# DSP_Power.net
KiCad netlist of a schematic drawn in Altium Designer
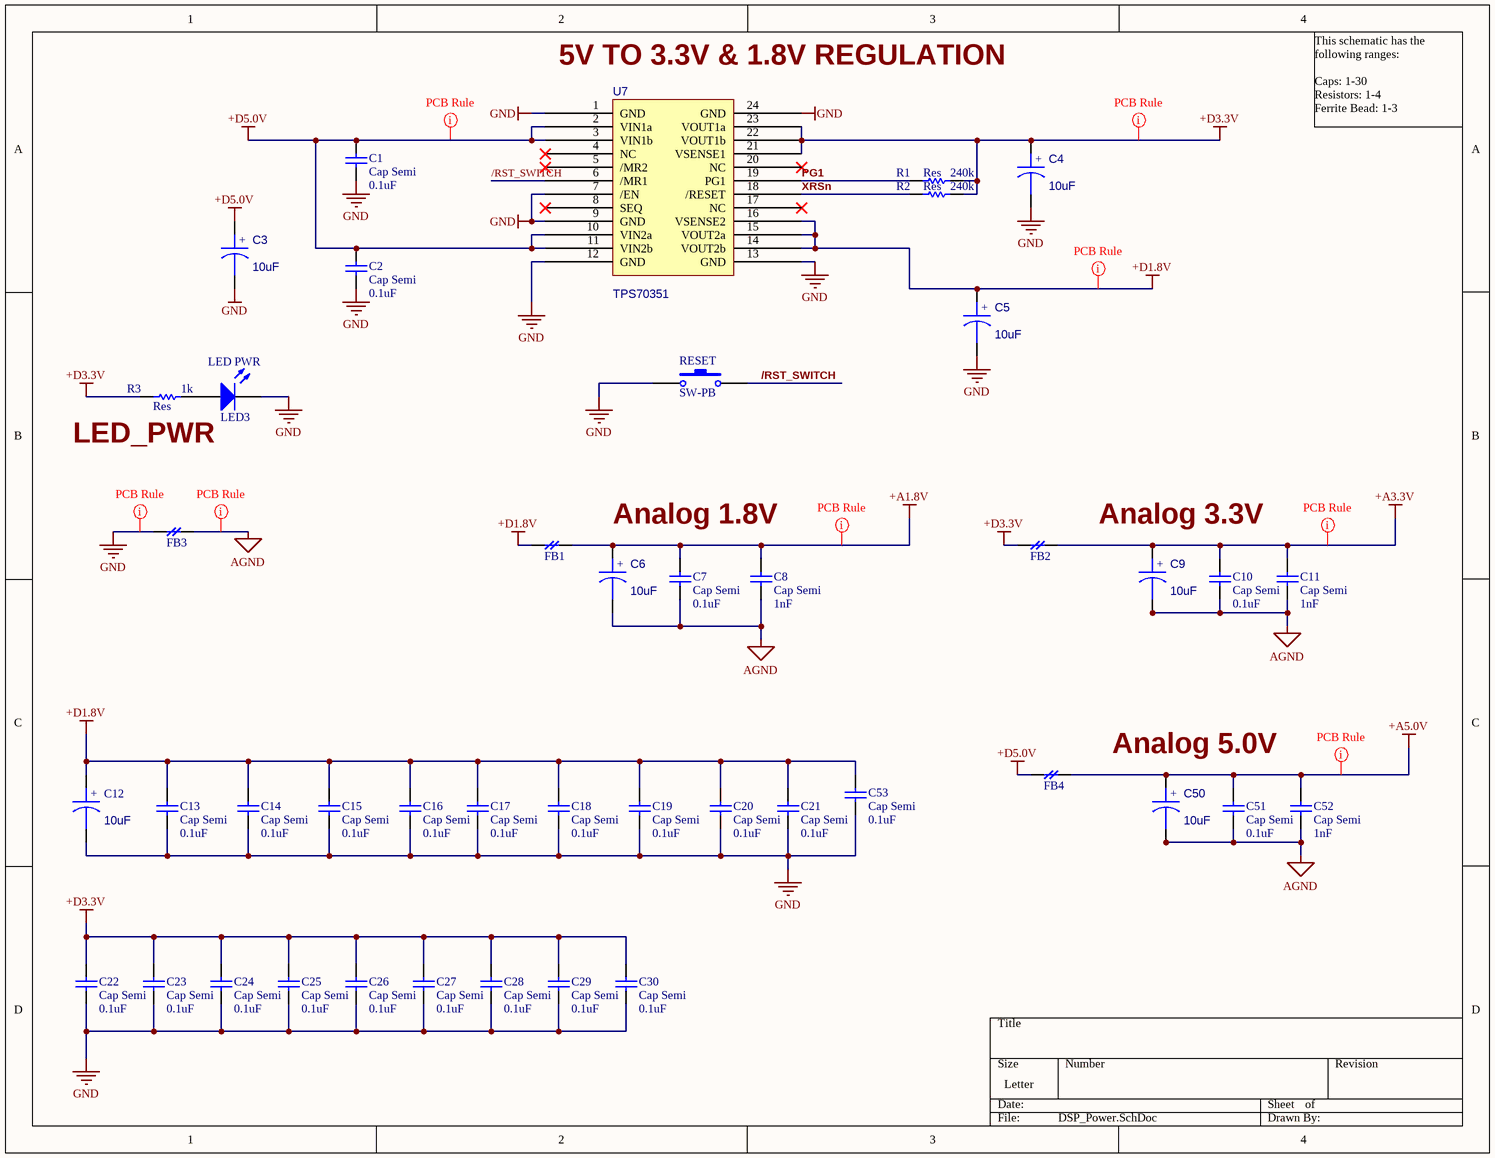
[diagram p0: DSP_Power.SchDoc]

(export (version "E")
  (design (tool "Eeschema 10.0.6"))
  (components
    (comp (ref "C1")
      (value "Cap Semi")
      (footprint "0805")
      (description "Capacitor (Semiconductor SIM Model)")
      (fields (field (name "ALTIUM_VALUE") "0.1uF") (field (name "PUBLISHER") "Altium Limited"))
      (libsource (lib "Miscellaneous Devices") (part "Cap Semi"))
    )
    (comp (ref "C2")
      (value "Cap Semi")
      (footprint "0805")
      (description "Capacitor (Semiconductor SIM Model)")
      (fields (field (name "ALTIUM_VALUE") "0.1uF") (field (name "PUBLISHER") "Altium Limited"))
      (libsource (lib "Miscellaneous Devices") (part "Cap Semi"))
    )
    (comp (ref "C3")
      (value "10uF")
      (footprint "3528")
      (description "digi-399-1563-1-ND")
      (libsource (lib "*") (part "CAPACITOR POL"))
    )
    (comp (ref "C4")
      (value "10uF")
      (footprint "3528")
      (description "digi-399-3096-1-ND")
      (libsource (lib "*") (part "CAPACITOR POL"))
    )
    (comp (ref "C5")
      (value "10uF")
      (footprint "3528")
      (description "digi-399-1576-1-ND")
      (libsource (lib "*") (part "CAPACITOR POL"))
    )
    (comp (ref "C6")
      (value "10uF")
      (footprint "3528")
      (description "digi-399-3096-1-ND")
      (libsource (lib "*") (part "CAPACITOR POL"))
    )
    (comp (ref "C7")
      (value "Cap Semi")
      (footprint "0805")
      (description "Capacitor (Semiconductor SIM Model)")
      (fields (field (name "ALTIUM_VALUE") "0.1uF") (field (name "PUBLISHER") "Altium Limited"))
      (libsource (lib "Miscellaneous Devices") (part "Cap Semi"))
    )
    (comp (ref "C8")
      (value "Cap Semi")
      (footprint "0805")
      (description "Capacitor (Semiconductor SIM Model)")
      (fields (field (name "ALTIUM_VALUE") "1nF") (field (name "PUBLISHER") "Altium Limited"))
      (libsource (lib "Miscellaneous Devices") (part "Cap Semi"))
    )
    (comp (ref "C9")
      (value "10uF")
      (footprint "3528")
      (description "digi-399-3096-1-ND")
      (libsource (lib "*") (part "CAPACITOR POL"))
    )
    (comp (ref "C10")
      (value "Cap Semi")
      (footprint "0805")
      (description "Capacitor (Semiconductor SIM Model)")
      (fields (field (name "ALTIUM_VALUE") "0.1uF") (field (name "PUBLISHER") "Altium Limited"))
      (libsource (lib "Miscellaneous Devices") (part "Cap Semi"))
    )
    (comp (ref "C11")
      (value "Cap Semi")
      (footprint "0805")
      (description "Capacitor (Semiconductor SIM Model)")
      (fields (field (name "ALTIUM_VALUE") "1nF") (field (name "PUBLISHER") "Altium Limited"))
      (libsource (lib "Miscellaneous Devices") (part "Cap Semi"))
    )
    (comp (ref "C12")
      (value "10uF")
      (footprint "3528")
      (description "digi-399-1576-1-ND")
      (libsource (lib "*") (part "CAPACITOR POL"))
    )
    (comp (ref "C13")
      (value "Cap Semi")
      (footprint "0805")
      (description "Capacitor (Semiconductor SIM Model)")
      (fields (field (name "ALTIUM_VALUE") "0.1uF") (field (name "PUBLISHER") "Altium Limited"))
      (libsource (lib "Miscellaneous Devices") (part "Cap Semi"))
    )
    (comp (ref "C14")
      (value "Cap Semi")
      (footprint "0805")
      (description "Capacitor (Semiconductor SIM Model)")
      (fields (field (name "ALTIUM_VALUE") "0.1uF") (field (name "PUBLISHER") "Altium Limited"))
      (libsource (lib "Miscellaneous Devices") (part "Cap Semi"))
    )
    (comp (ref "C15")
      (value "Cap Semi")
      (footprint "0805")
      (description "Capacitor (Semiconductor SIM Model)")
      (fields (field (name "ALTIUM_VALUE") "0.1uF") (field (name "PUBLISHER") "Altium Limited"))
      (libsource (lib "Miscellaneous Devices") (part "Cap Semi"))
    )
    (comp (ref "C16")
      (value "Cap Semi")
      (footprint "0805")
      (description "Capacitor (Semiconductor SIM Model)")
      (fields (field (name "ALTIUM_VALUE") "0.1uF") (field (name "PUBLISHER") "Altium Limited"))
      (libsource (lib "Miscellaneous Devices") (part "Cap Semi"))
    )
    (comp (ref "C17")
      (value "Cap Semi")
      (footprint "0805")
      (description "Capacitor (Semiconductor SIM Model)")
      (fields (field (name "ALTIUM_VALUE") "0.1uF") (field (name "PUBLISHER") "Altium Limited"))
      (libsource (lib "Miscellaneous Devices") (part "Cap Semi"))
    )
    (comp (ref "C18")
      (value "Cap Semi")
      (footprint "0805")
      (description "Capacitor (Semiconductor SIM Model)")
      (fields (field (name "ALTIUM_VALUE") "0.1uF") (field (name "PUBLISHER") "Altium Limited"))
      (libsource (lib "Miscellaneous Devices") (part "Cap Semi"))
    )
    (comp (ref "C19")
      (value "Cap Semi")
      (footprint "0805")
      (description "Capacitor (Semiconductor SIM Model)")
      (fields (field (name "ALTIUM_VALUE") "0.1uF") (field (name "PUBLISHER") "Altium Limited"))
      (libsource (lib "Miscellaneous Devices") (part "Cap Semi"))
    )
    (comp (ref "C20")
      (value "Cap Semi")
      (footprint "0805")
      (description "Capacitor (Semiconductor SIM Model)")
      (fields (field (name "ALTIUM_VALUE") "0.1uF") (field (name "PUBLISHER") "Altium Limited"))
      (libsource (lib "Miscellaneous Devices") (part "Cap Semi"))
    )
    (comp (ref "C21")
      (value "Cap Semi")
      (footprint "0805")
      (description "Capacitor (Semiconductor SIM Model)")
      (fields (field (name "ALTIUM_VALUE") "0.1uF") (field (name "PUBLISHER") "Altium Limited"))
      (libsource (lib "Miscellaneous Devices") (part "Cap Semi"))
    )
    (comp (ref "C22")
      (value "Cap Semi")
      (footprint "0805")
      (description "Capacitor (Semiconductor SIM Model)")
      (fields (field (name "ALTIUM_VALUE") "0.1uF") (field (name "PUBLISHER") "Altium Limited"))
      (libsource (lib "Miscellaneous Devices") (part "Cap Semi"))
    )
    (comp (ref "C23")
      (value "Cap Semi")
      (footprint "0805")
      (description "Capacitor (Semiconductor SIM Model)")
      (fields (field (name "ALTIUM_VALUE") "0.1uF") (field (name "PUBLISHER") "Altium Limited"))
      (libsource (lib "Miscellaneous Devices") (part "Cap Semi"))
    )
    (comp (ref "C24")
      (value "Cap Semi")
      (footprint "0805")
      (description "Capacitor (Semiconductor SIM Model)")
      (fields (field (name "ALTIUM_VALUE") "0.1uF") (field (name "PUBLISHER") "Altium Limited"))
      (libsource (lib "Miscellaneous Devices") (part "Cap Semi"))
    )
    (comp (ref "C25")
      (value "Cap Semi")
      (footprint "0805")
      (description "Capacitor (Semiconductor SIM Model)")
      (fields (field (name "ALTIUM_VALUE") "0.1uF") (field (name "PUBLISHER") "Altium Limited"))
      (libsource (lib "Miscellaneous Devices") (part "Cap Semi"))
    )
    (comp (ref "C26")
      (value "Cap Semi")
      (footprint "0805")
      (description "Capacitor (Semiconductor SIM Model)")
      (fields (field (name "ALTIUM_VALUE") "0.1uF") (field (name "PUBLISHER") "Altium Limited"))
      (libsource (lib "Miscellaneous Devices") (part "Cap Semi"))
    )
    (comp (ref "C27")
      (value "Cap Semi")
      (footprint "0805")
      (description "Capacitor (Semiconductor SIM Model)")
      (fields (field (name "ALTIUM_VALUE") "0.1uF") (field (name "PUBLISHER") "Altium Limited"))
      (libsource (lib "Miscellaneous Devices") (part "Cap Semi"))
    )
    (comp (ref "C28")
      (value "Cap Semi")
      (footprint "0805")
      (description "Capacitor (Semiconductor SIM Model)")
      (fields (field (name "ALTIUM_VALUE") "0.1uF") (field (name "PUBLISHER") "Altium Limited"))
      (libsource (lib "Miscellaneous Devices") (part "Cap Semi"))
    )
    (comp (ref "C29")
      (value "Cap Semi")
      (footprint "0805")
      (description "Capacitor (Semiconductor SIM Model)")
      (fields (field (name "ALTIUM_VALUE") "0.1uF") (field (name "PUBLISHER") "Altium Limited"))
      (libsource (lib "Miscellaneous Devices") (part "Cap Semi"))
    )
    (comp (ref "C30")
      (value "Cap Semi")
      (footprint "0805")
      (description "Capacitor (Semiconductor SIM Model)")
      (fields (field (name "ALTIUM_VALUE") "0.1uF") (field (name "PUBLISHER") "Altium Limited"))
      (libsource (lib "Miscellaneous Devices") (part "Cap Semi"))
    )
    (comp (ref "C50")
      (value "10uF")
      (footprint "3528")
      (description "digi-399-3096-1-ND")
      (libsource (lib "*") (part "CAPACITOR POL"))
    )
    (comp (ref "C51")
      (value "Cap Semi")
      (footprint "0805")
      (description "Capacitor (Semiconductor SIM Model)")
      (fields (field (name "ALTIUM_VALUE") "0.1uF") (field (name "PUBLISHER") "Altium Limited"))
      (libsource (lib "Miscellaneous Devices") (part "Cap Semi"))
    )
    (comp (ref "C52")
      (value "Cap Semi")
      (footprint "0805")
      (description "Capacitor (Semiconductor SIM Model)")
      (fields (field (name "ALTIUM_VALUE") "1nF") (field (name "PUBLISHER") "Altium Limited"))
      (libsource (lib "Miscellaneous Devices") (part "Cap Semi"))
    )
    (comp (ref "C53")
      (value "Cap Semi")
      (footprint "0805")
      (description "Capacitor (Semiconductor SIM Model)")
      (fields (field (name "ALTIUM_VALUE") "0.1uF") (field (name "PUBLISHER") "Altium Limited"))
      (libsource (lib "Miscellaneous Devices") (part "Cap Semi"))
    )
    (comp (ref "FB1")
      (value "Ferrite_Bead")
      (footprint "CR2012-0805")
      (description "Ferrite Bead")
      (libsource (lib "addl") (part "Ferrite_Bead"))
    )
    (comp (ref "FB2")
      (value "Ferrite_Bead")
      (footprint "CR2012-0805")
      (description "Ferrite Bead")
      (libsource (lib "addl") (part "Ferrite_Bead"))
    )
    (comp (ref "FB3")
      (value "Ferrite_Bead")
      (footprint "CR2012-0805")
      (description "Ferrite Bead")
      (libsource (lib "addl") (part "Ferrite_Bead"))
    )
    (comp (ref "FB4")
      (value "Ferrite_Bead")
      (footprint "CR2012-0805")
      (description "Ferrite Bead")
      (libsource (lib "addl") (part "Ferrite_Bead"))
    )
    (comp (ref "LED PWR")
      (value "LED3")
      (footprint "0805")
      (description "Typical BLUE SiC LED")
      (fields (field (name "PUBLISHER") "Altium Limited"))
      (libsource (lib "Miscellaneous Devices") (part "LED3"))
    )
    (comp (ref "R1")
      (value "Res")
      (footprint "0805")
      (description "Semiconductor Resistor")
      (fields (field (name "ALTIUM_VALUE") "240k") (field (name "PUBLISHER") "Altium Limited"))
      (libsource (lib "F28335_DSC_Breakout") (part "Res Semi"))
    )
    (comp (ref "R2")
      (value "Res")
      (footprint "0805")
      (description "Semiconductor Resistor")
      (fields (field (name "ALTIUM_VALUE") "240k") (field (name "PUBLISHER") "Altium Limited"))
      (libsource (lib "F28335_DSC_Breakout") (part "Res Semi"))
    )
    (comp (ref "R3")
      (value "Res")
      (footprint "0805")
      (description "Semiconductor Resistor")
      (fields (field (name "ALTIUM_VALUE") "1k") (field (name "PUBLISHER") "Altium Limited"))
      (libsource (lib "F28335_DSC_Breakout") (part "Res Semi"))
    )
    (comp (ref "RESET")
      (value "SW-PB")
      (footprint "SWITCH_2PAD_SMD")
      (description "Switch")
      (fields (field (name "PUBLISHER") "Altium Limited"))
      (libsource (lib "Miscellaneous Devices") (part "SW-PB"))
    )
    (comp (ref "U7")
      (value "TPS70351")
      (footprint "PWP24")
      (description "IC 3.3V/1.8V LDO REG 24-HTSSOP")
      (libsource (lib "F28335_DSC_Breakout") (part "TPS70351"))
    )
  )
  (nets
    (net (code "1") (name "+A1.8V") (class "Default")
      (node (ref "C6") (pin "1") (pinfunction "1_1") (pintype "passive"))
      (node (ref "C7") (pin "2") (pinfunction "2_2") (pintype "passive"))
      (node (ref "C8") (pin "2") (pinfunction "2_2") (pintype "passive"))
      (node (ref "FB1") (pin "2") (pinfunction "2_2") (pintype "passive"))
    )
    (net (code "2") (name "+A3.3V") (class "Default")
      (node (ref "C10") (pin "2") (pinfunction "2_2") (pintype "passive"))
      (node (ref "C11") (pin "2") (pinfunction "2_2") (pintype "passive"))
      (node (ref "C9") (pin "1") (pinfunction "1_1") (pintype "passive"))
      (node (ref "FB2") (pin "2") (pinfunction "2_2") (pintype "passive"))
    )
    (net (code "3") (name "+A5.0V") (class "Default")
      (node (ref "C50") (pin "1") (pinfunction "1_1") (pintype "passive"))
      (node (ref "C51") (pin "2") (pinfunction "2_2") (pintype "passive"))
      (node (ref "C52") (pin "2") (pinfunction "2_2") (pintype "passive"))
      (node (ref "FB4") (pin "2") (pinfunction "2_2") (pintype "passive"))
    )
    (net (code "4") (name "+D1.8V") (class "Default")
      (node (ref "C12") (pin "1") (pinfunction "1_1") (pintype "passive"))
      (node (ref "C13") (pin "2") (pinfunction "2_2") (pintype "passive"))
      (node (ref "C14") (pin "2") (pinfunction "2_2") (pintype "passive"))
      (node (ref "C15") (pin "2") (pinfunction "2_2") (pintype "passive"))
      (node (ref "C16") (pin "2") (pinfunction "2_2") (pintype "passive"))
      (node (ref "C17") (pin "2") (pinfunction "2_2") (pintype "passive"))
      (node (ref "C18") (pin "2") (pinfunction "2_2") (pintype "passive"))
      (node (ref "C19") (pin "2") (pinfunction "2_2") (pintype "passive"))
      (node (ref "C20") (pin "2") (pinfunction "2_2") (pintype "passive"))
      (node (ref "C21") (pin "2") (pinfunction "2_2") (pintype "passive"))
      (node (ref "C5") (pin "1") (pinfunction "1_1") (pintype "passive"))
      (node (ref "C53") (pin "2") (pinfunction "2_2") (pintype "passive"))
      (node (ref "FB1") (pin "1") (pinfunction "1_1") (pintype "passive"))
      (node (ref "U7") (pin "14") (pinfunction "VOUT2b_14") (pintype "passive"))
      (node (ref "U7") (pin "15") (pinfunction "VOUT2a_15") (pintype "passive"))
      (node (ref "U7") (pin "16") (pinfunction "VSENSE2_16") (pintype "passive"))
    )
    (net (code "5") (name "+D3.3V") (class "Default")
      (node (ref "C22") (pin "2") (pinfunction "2_2") (pintype "passive"))
      (node (ref "C23") (pin "2") (pinfunction "2_2") (pintype "passive"))
      (node (ref "C24") (pin "2") (pinfunction "2_2") (pintype "passive"))
      (node (ref "C25") (pin "2") (pinfunction "2_2") (pintype "passive"))
      (node (ref "C26") (pin "2") (pinfunction "2_2") (pintype "passive"))
      (node (ref "C27") (pin "2") (pinfunction "2_2") (pintype "passive"))
      (node (ref "C28") (pin "2") (pinfunction "2_2") (pintype "passive"))
      (node (ref "C29") (pin "2") (pinfunction "2_2") (pintype "passive"))
      (node (ref "C30") (pin "2") (pinfunction "2_2") (pintype "passive"))
      (node (ref "C4") (pin "1") (pinfunction "1_1") (pintype "passive"))
      (node (ref "FB2") (pin "1") (pinfunction "1_1") (pintype "passive"))
      (node (ref "R1") (pin "2") (pinfunction "2_2") (pintype "passive"))
      (node (ref "R2") (pin "2") (pinfunction "2_2") (pintype "passive"))
      (node (ref "R3") (pin "1") (pinfunction "1_1") (pintype "passive"))
      (node (ref "U7") (pin "21") (pinfunction "VSENSE1_21") (pintype "passive"))
      (node (ref "U7") (pin "22") (pinfunction "VOUT1b_22") (pintype "passive"))
      (node (ref "U7") (pin "23") (pinfunction "VOUT1a_23") (pintype "passive"))
    )
    (net (code "6") (name "+D5.0V") (class "Default")
      (node (ref "C1") (pin "2") (pinfunction "2_2") (pintype "passive"))
      (node (ref "C2") (pin "2") (pinfunction "2_2") (pintype "passive"))
      (node (ref "C3") (pin "1") (pinfunction "1_1") (pintype "passive"))
      (node (ref "FB4") (pin "1") (pinfunction "1_1") (pintype "passive"))
      (node (ref "U7") (pin "10") (pinfunction "VIN2a_10") (pintype "passive"))
      (node (ref "U7") (pin "11") (pinfunction "VIN2b_11") (pintype "passive"))
      (node (ref "U7") (pin "2") (pinfunction "VIN1a_2") (pintype "passive"))
      (node (ref "U7") (pin "3") (pinfunction "VIN1b_3") (pintype "passive"))
    )
    (net (code "7") (name "/PG1") (class "Default")
      (node (ref "R1") (pin "1") (pinfunction "1_1") (pintype "passive"))
      (node (ref "U7") (pin "19") (pinfunction "PG1_19") (pintype "passive"))
    )
    (net (code "8") (name "/XRSn") (class "Default")
      (node (ref "R2") (pin "1") (pinfunction "1_1") (pintype "passive"))
      (node (ref "U7") (pin "18") (pinfunction "/RESET_18") (pintype "passive"))
    )
    (net (code "9") (name "/{slash}RST_SWITCH") (class "Default")
      (node (ref "RESET") (pin "2") (pinfunction "2_2") (pintype "passive"))
      (node (ref "U7") (pin "6") (pinfunction "/MR1_6") (pintype "passive"))
    )
    (net (code "10") (name "AGND") (class "Default")
      (node (ref "C10") (pin "1") (pinfunction "1_1") (pintype "passive"))
      (node (ref "C11") (pin "1") (pinfunction "1_1") (pintype "passive"))
      (node (ref "C50") (pin "2") (pinfunction "2_2") (pintype "passive"))
      (node (ref "C51") (pin "1") (pinfunction "1_1") (pintype "passive"))
      (node (ref "C52") (pin "1") (pinfunction "1_1") (pintype "passive"))
      (node (ref "C6") (pin "2") (pinfunction "2_2") (pintype "passive"))
      (node (ref "C7") (pin "1") (pinfunction "1_1") (pintype "passive"))
      (node (ref "C8") (pin "1") (pinfunction "1_1") (pintype "passive"))
      (node (ref "C9") (pin "2") (pinfunction "2_2") (pintype "passive"))
      (node (ref "FB3") (pin "2") (pinfunction "2_2") (pintype "passive"))
    )
    (net (code "11") (name "GND") (class "Default")
      (node (ref "C1") (pin "1") (pinfunction "1_1") (pintype "passive"))
      (node (ref "C12") (pin "2") (pinfunction "2_2") (pintype "passive"))
      (node (ref "C13") (pin "1") (pinfunction "1_1") (pintype "passive"))
      (node (ref "C14") (pin "1") (pinfunction "1_1") (pintype "passive"))
      (node (ref "C15") (pin "1") (pinfunction "1_1") (pintype "passive"))
      (node (ref "C16") (pin "1") (pinfunction "1_1") (pintype "passive"))
      (node (ref "C17") (pin "1") (pinfunction "1_1") (pintype "passive"))
      (node (ref "C18") (pin "1") (pinfunction "1_1") (pintype "passive"))
      (node (ref "C19") (pin "1") (pinfunction "1_1") (pintype "passive"))
      (node (ref "C2") (pin "1") (pinfunction "1_1") (pintype "passive"))
      (node (ref "C20") (pin "1") (pinfunction "1_1") (pintype "passive"))
      (node (ref "C21") (pin "1") (pinfunction "1_1") (pintype "passive"))
      (node (ref "C22") (pin "1") (pinfunction "1_1") (pintype "passive"))
      (node (ref "C23") (pin "1") (pinfunction "1_1") (pintype "passive"))
      (node (ref "C24") (pin "1") (pinfunction "1_1") (pintype "passive"))
      (node (ref "C25") (pin "1") (pinfunction "1_1") (pintype "passive"))
      (node (ref "C26") (pin "1") (pinfunction "1_1") (pintype "passive"))
      (node (ref "C27") (pin "1") (pinfunction "1_1") (pintype "passive"))
      (node (ref "C28") (pin "1") (pinfunction "1_1") (pintype "passive"))
      (node (ref "C29") (pin "1") (pinfunction "1_1") (pintype "passive"))
      (node (ref "C3") (pin "2") (pinfunction "2_2") (pintype "passive"))
      (node (ref "C30") (pin "1") (pinfunction "1_1") (pintype "passive"))
      (node (ref "C4") (pin "2") (pinfunction "2_2") (pintype "passive"))
      (node (ref "C5") (pin "2") (pinfunction "2_2") (pintype "passive"))
      (node (ref "C53") (pin "1") (pinfunction "1_1") (pintype "passive"))
      (node (ref "FB3") (pin "1") (pinfunction "1_1") (pintype "passive"))
      (node (ref "LED PWR") (pin "2") (pinfunction "K_2") (pintype "passive"))
      (node (ref "RESET") (pin "1") (pinfunction "1_1") (pintype "passive"))
      (node (ref "U7") (pin "1") (pinfunction "GND_1") (pintype "passive"))
      (node (ref "U7") (pin "12") (pinfunction "GND_12") (pintype "passive"))
      (node (ref "U7") (pin "13") (pinfunction "GND_13") (pintype "passive"))
      (node (ref "U7") (pin "24") (pinfunction "GND_24") (pintype "passive"))
      (node (ref "U7") (pin "7") (pinfunction "/EN_7") (pintype "passive"))
      (node (ref "U7") (pin "9") (pinfunction "GND_9") (pintype "passive"))
    )
    (net (code "12") (name "Net-(LED PWR-A)") (class "Default")
      (node (ref "LED PWR") (pin "1") (pinfunction "A_1") (pintype "passive"))
      (node (ref "R3") (pin "2") (pinfunction "2_2") (pintype "passive"))
    )
    (net (code "13") (name "unconnected-(U7-NC-Pad4)") (class "Default")
      (node (ref "U7") (pin "4") (pinfunction "NC_4") (pintype "passive+no_connect"))
    )
    (net (code "14") (name "unconnected-(U7-NC-Pad17)") (class "Default")
      (node (ref "U7") (pin "17") (pinfunction "NC_17") (pintype "passive+no_connect"))
    )
    (net (code "15") (name "unconnected-(U7-NC-Pad20)") (class "Default")
      (node (ref "U7") (pin "20") (pinfunction "NC_20") (pintype "passive+no_connect"))
    )
    (net (code "16") (name "unconnected-(U7-SEQ-Pad8)") (class "Default")
      (node (ref "U7") (pin "8") (pinfunction "SEQ_8") (pintype "passive+no_connect"))
    )
    (net (code "17") (name "unconnected-(U7-{slash}MR2-Pad5)") (class "Default")
      (node (ref "U7") (pin "5") (pinfunction "/MR2_5") (pintype "passive+no_connect"))
    )
  )
)
